# powersupply.net
KiCad netlist of a schematic drawn in EAGLE
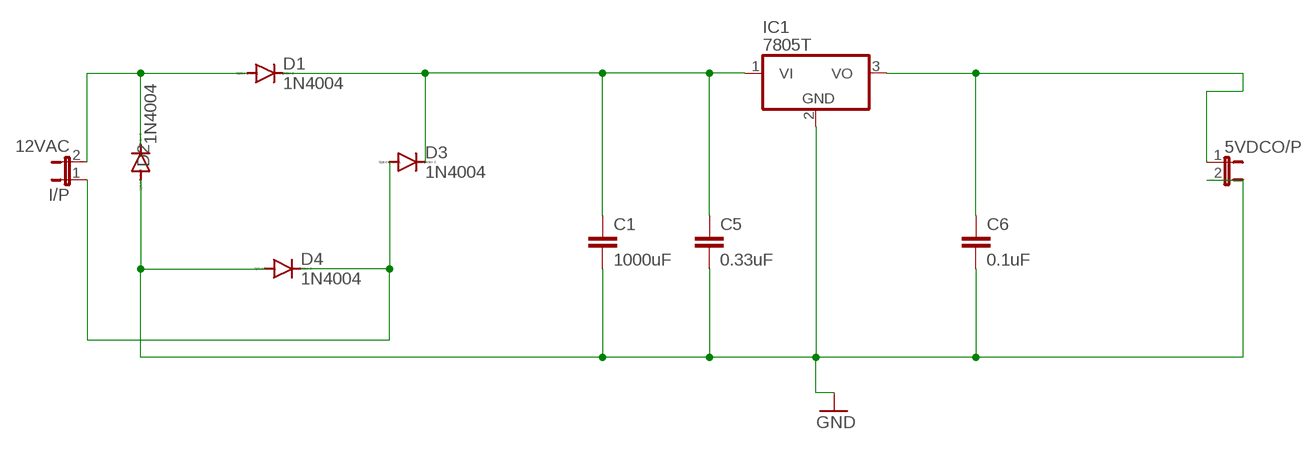
[diagram p0: schematic, sheet 1]

(export (version "E")
  (design (tool "Eeschema 10.0.6"))
  (components
    (comp (ref "5VDCO/P")
      (value "JP1E")
      (footprint "eagle-import:JP1")
      (libsource (lib "eagle-import") (part "JP1E"))
    )
    (comp (ref "C1")
      (value "1000uF")
      (footprint "eagle-import:C2.5-3")
      (libsource (lib "eagle-import") (part "C2,5-3"))
    )
    (comp (ref "C5")
      (value "0.33uF")
      (footprint "eagle-import:C2.5-3")
      (libsource (lib "eagle-import") (part "C2,5-3"))
    )
    (comp (ref "C6")
      (value "0.1uF")
      (footprint "eagle-import:C2.5-3")
      (libsource (lib "eagle-import") (part "C2,5-3"))
    )
    (comp (ref "D1")
      (value "1N4004")
      (footprint "eagle-import:DO41-10")
      (libsource (lib "eagle-import") (part "1N4004"))
    )
    (comp (ref "D2")
      (value "1N4004")
      (footprint "eagle-import:DO41-10")
      (libsource (lib "eagle-import") (part "1N4004"))
    )
    (comp (ref "D3")
      (value "1N4004")
      (footprint "eagle-import:DO41-10")
      (libsource (lib "eagle-import") (part "1N4004"))
    )
    (comp (ref "D4")
      (value "1N4004")
      (footprint "eagle-import:DO41-10")
      (libsource (lib "eagle-import") (part "1N4004"))
    )
    (comp (ref "I/P")
      (value "12VAC")
      (footprint "eagle-import:JP1")
      (libsource (lib "eagle-import") (part "JP1E"))
    )
    (comp (ref "IC1")
      (value "7805T")
      (footprint "eagle-import:TO220H")
      (libsource (lib "eagle-import") (part "78T05"))
    )
  )
  (nets
    (net (code "1") (name "GND") (class "Default")
      (node (ref "5VDCO/P") (pin "2") (pinfunction "2_2") (pintype "passive"))
      (node (ref "C1") (pin "2") (pinfunction "2_2") (pintype "passive"))
      (node (ref "C5") (pin "2") (pinfunction "2_2") (pintype "passive"))
      (node (ref "C6") (pin "2") (pinfunction "2_2") (pintype "passive"))
      (node (ref "D2") (pin "A") (pinfunction "A_A") (pintype "passive"))
      (node (ref "D4") (pin "A") (pinfunction "A_A") (pintype "passive"))
      (node (ref "IC1") (pin "2") (pinfunction "GND_2") (pintype "passive"))
    )
    (net (code "2") (name "Net-(D1-PadA)") (class "Default")
      (node (ref "D1") (pin "A") (pinfunction "A_A") (pintype "passive"))
      (node (ref "D2") (pin "C") (pinfunction "C_C") (pintype "passive"))
      (node (ref "I/P") (pin "2") (pinfunction "2_2") (pintype "passive"))
    )
    (net (code "3") (name "Net-(D3-PadA)") (class "Default")
      (node (ref "D3") (pin "A") (pinfunction "A_A") (pintype "passive"))
      (node (ref "D4") (pin "C") (pinfunction "C_C") (pintype "passive"))
      (node (ref "I/P") (pin "1") (pinfunction "1_1") (pintype "passive"))
    )
    (net (code "4") (name "Net-(IC1-VI)") (class "Default")
      (node (ref "C1") (pin "1") (pinfunction "1_1") (pintype "passive"))
      (node (ref "C5") (pin "1") (pinfunction "1_1") (pintype "passive"))
      (node (ref "D1") (pin "C") (pinfunction "C_C") (pintype "passive"))
      (node (ref "D3") (pin "C") (pinfunction "C_C") (pintype "passive"))
      (node (ref "IC1") (pin "1") (pinfunction "VI_1") (pintype "input"))
    )
    (net (code "5") (name "Net-(IC1-VO)") (class "Default")
      (node (ref "5VDCO/P") (pin "1") (pinfunction "1_1") (pintype "passive"))
      (node (ref "C6") (pin "1") (pinfunction "1_1") (pintype "passive"))
      (node (ref "IC1") (pin "3") (pinfunction "VO_3") (pintype "passive"))
    )
  )
)
